# Fascia_physioBoardV0.net
KiCad netlist of a schematic drawn in EAGLE
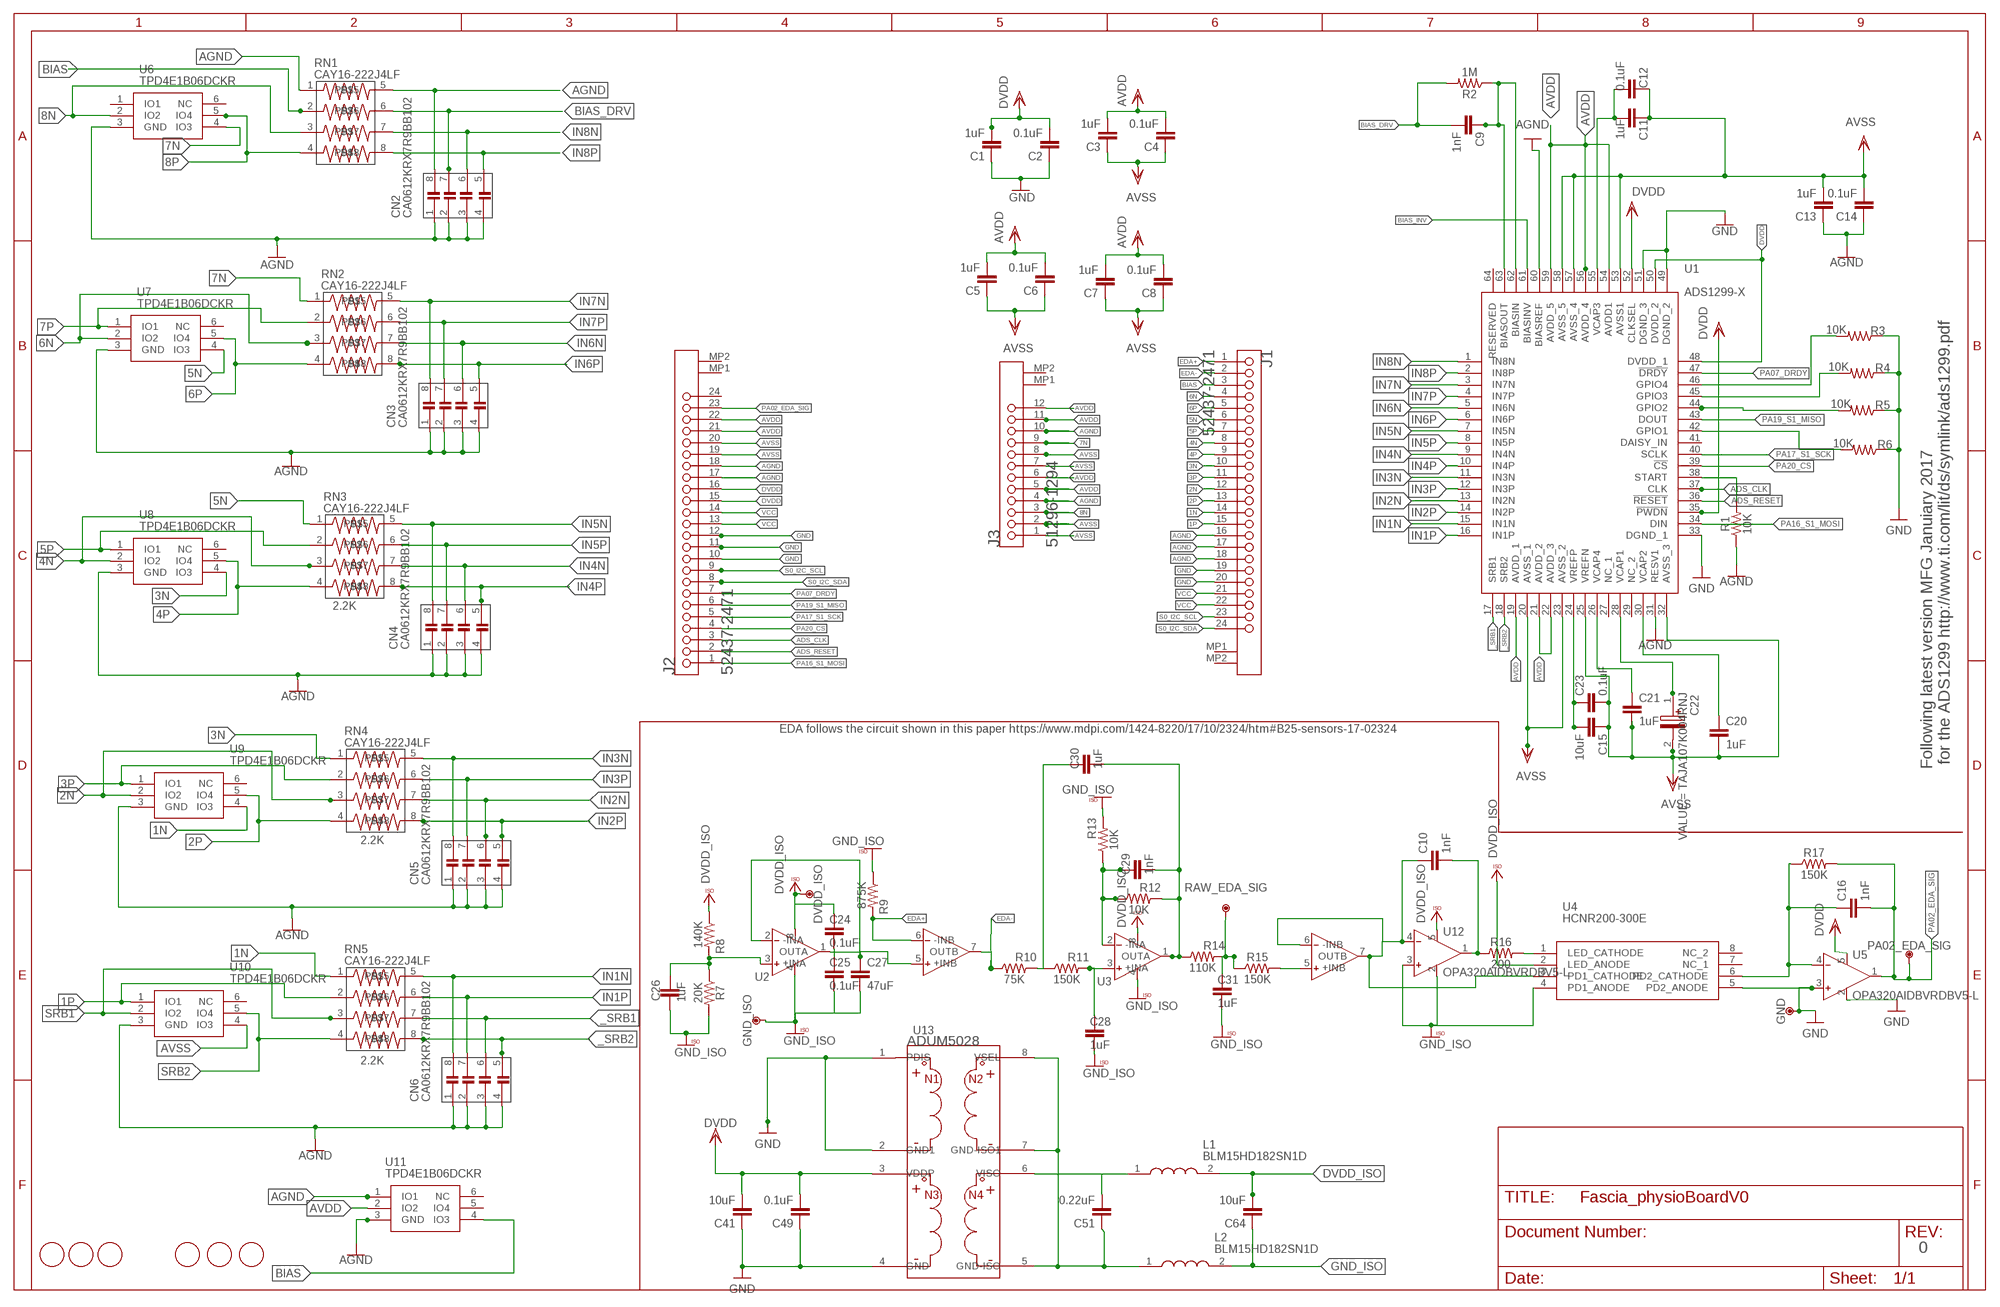
[diagram p0: schematic, sheet 1]

(export (version "E")
  (design (tool "Eeschema 10.0.6"))
  (components
    (comp (ref "C1")
      (value "1uF")
      (footprint "eagle-import:0402-TIGHT")
      (libsource (lib "eagle-import") (part "1UF-0402T-16V-10%"))
    )
    (comp (ref "C2")
      (value "0.1uF")
      (footprint "eagle-import:0402-TIGHT")
      (libsource (lib "eagle-import") (part "0.1UF-0402T-16V-10%"))
    )
    (comp (ref "C3")
      (value "1uF")
      (footprint "eagle-import:0402-TIGHT")
      (libsource (lib "eagle-import") (part "1UF-0402T-16V-10%"))
    )
    (comp (ref "C4")
      (value "0.1uF")
      (footprint "eagle-import:0402-TIGHT")
      (libsource (lib "eagle-import") (part "0.1UF-0402T-16V-10%"))
    )
    (comp (ref "C5")
      (value "1uF")
      (footprint "eagle-import:0402-TIGHT")
      (libsource (lib "eagle-import") (part "1UF-0402T-16V-10%"))
    )
    (comp (ref "C6")
      (value "0.1uF")
      (footprint "eagle-import:0402-TIGHT")
      (libsource (lib "eagle-import") (part "0.1UF-0402T-16V-10%"))
    )
    (comp (ref "C7")
      (value "1uF")
      (footprint "eagle-import:0402-TIGHT")
      (libsource (lib "eagle-import") (part "1UF-0402T-16V-10%"))
    )
    (comp (ref "C8")
      (value "0.1uF")
      (footprint "eagle-import:0402-TIGHT")
      (libsource (lib "eagle-import") (part "0.1UF-0402T-16V-10%"))
    )
    (comp (ref "C9")
      (value "1nF")
      (footprint "eagle-import:0402-TIGHT")
      (libsource (lib "eagle-import") (part "1NF-0402T-16V-10%"))
    )
    (comp (ref "C10")
      (value "1nF")
      (footprint "eagle-import:0402-TIGHT")
      (libsource (lib "eagle-import") (part "1NF-0402T-16V-10%"))
    )
    (comp (ref "C11")
      (value "1uF")
      (footprint "eagle-import:0402-TIGHT")
      (libsource (lib "eagle-import") (part "1UF-0402T-16V-10%"))
    )
    (comp (ref "C12")
      (value "0.1uF")
      (footprint "eagle-import:0402-TIGHT")
      (libsource (lib "eagle-import") (part "0.1UF-0402T-16V-10%"))
    )
    (comp (ref "C13")
      (value "1uF")
      (footprint "eagle-import:0402-TIGHT")
      (libsource (lib "eagle-import") (part "1UF-0402T-16V-10%"))
    )
    (comp (ref "C14")
      (value "0.1uF")
      (footprint "eagle-import:0402-TIGHT")
      (libsource (lib "eagle-import") (part "0.1UF-0402T-16V-10%"))
    )
    (comp (ref "C15")
      (value "10uF")
      (footprint "eagle-import:0402")
      (libsource (lib "eagle-import") (part "0.1UF-0402-16V-10%"))
    )
    (comp (ref "C16")
      (value "1nF")
      (footprint "eagle-import:0402-TIGHT")
      (libsource (lib "eagle-import") (part "1NF-0402T-16V-10%"))
    )
    (comp (ref "C20")
      (value "1uF")
      (footprint "eagle-import:0402-TIGHT")
      (libsource (lib "eagle-import") (part "1UF-0402T-16V-10%"))
    )
    (comp (ref "C21")
      (value "1uF")
      (footprint "eagle-import:0402-TIGHT")
      (libsource (lib "eagle-import") (part "1UF-0402T-16V-10%"))
    )
    (comp (ref "C22")
      (value "TAJA107K004RNJ")
      (footprint "eagle-import:CAPPM3216X180N")
      (fields
        (field (name "MOUSER_PART_NUMBER") "581-TAJA107K004RNJ")
        (field (name "RS_PART_NUMBER") "1360130")
      )
      (libsource (lib "eagle-import") (part "TAJA107K004RNJ"))
    )
    (comp (ref "C23")
      (value "0.1uF")
      (footprint "eagle-import:0402-TIGHT")
      (libsource (lib "eagle-import") (part "0.1UF-0402T-16V-10%"))
    )
    (comp (ref "C24")
      (value "0.1uF")
      (footprint "eagle-import:0402-TIGHT")
      (libsource (lib "eagle-import") (part "0.1UF-0402T-16V-10%"))
    )
    (comp (ref "C25")
      (value "0.1uF")
      (footprint "eagle-import:0402-TIGHT")
      (libsource (lib "eagle-import") (part "0.1UF-0402T-16V-10%"))
    )
    (comp (ref "C26")
      (value "1uF")
      (footprint "eagle-import:0402-TIGHT")
      (libsource (lib "eagle-import") (part "1UF-0402T-16V-10%"))
    )
    (comp (ref "C27")
      (value "47uF")
      (footprint "eagle-import:0603")
      (libsource (lib "eagle-import") (part "47UF-0603-25V-5%"))
    )
    (comp (ref "C28")
      (value "1uF")
      (footprint "eagle-import:0402-TIGHT")
      (libsource (lib "eagle-import") (part "1UF-0402T-16V-10%"))
    )
    (comp (ref "C29")
      (value "1nF")
      (footprint "eagle-import:0402-TIGHT")
      (libsource (lib "eagle-import") (part "1NF-0402T-16V-10%"))
    )
    (comp (ref "C30")
      (value "1uF")
      (footprint "eagle-import:0402-TIGHT")
      (libsource (lib "eagle-import") (part "1UF-0402T-16V-10%"))
    )
    (comp (ref "C31")
      (value "1uF")
      (footprint "eagle-import:0402-TIGHT")
      (libsource (lib "eagle-import") (part "1UF-0402T-16V-10%"))
    )
    (comp (ref "C41")
      (value "10uF")
      (footprint "eagle-import:0603")
      (libsource (lib "eagle-import") (part "10UF-0603-6.3V-20%"))
    )
    (comp (ref "C49")
      (value "0.1uF")
      (footprint "eagle-import:0402-TIGHT")
      (libsource (lib "eagle-import") (part "0.1UF-0402T-16V-10%"))
    )
    (comp (ref "C51")
      (value "0.22uF")
      (footprint "eagle-import:0402-TIGHT")
      (libsource (lib "eagle-import") (part "0.22UF-0402T-16V-10%"))
    )
    (comp (ref "C64")
      (value "10uF")
      (footprint "eagle-import:0603")
      (libsource (lib "eagle-import") (part "10UF-0603-6.3V-20%"))
    )
    (comp (ref "CN2")
      (value "CA0612KRX7R9BB102")
      (footprint "eagle-import:CA0612KRX7R9BB102")
      (fields
        (field (name "MOUSER_PART_NUMBER") "603-CA612KRX7R9BB102")
        (field (name "RS_PART_NUMBER") "6169789")
      )
      (libsource (lib "eagle-import") (part "CA0612KRX7R9BB102"))
    )
    (comp (ref "CN3")
      (value "CA0612KRX7R9BB102")
      (footprint "eagle-import:CA0612KRX7R9BB102")
      (fields
        (field (name "MOUSER_PART_NUMBER") "603-CA612KRX7R9BB102")
        (field (name "RS_PART_NUMBER") "6169789")
      )
      (libsource (lib "eagle-import") (part "CA0612KRX7R9BB102"))
    )
    (comp (ref "CN4")
      (value "CA0612KRX7R9BB102")
      (footprint "eagle-import:CA0612KRX7R9BB102")
      (fields
        (field (name "MOUSER_PART_NUMBER") "603-CA612KRX7R9BB102")
        (field (name "RS_PART_NUMBER") "6169789")
      )
      (libsource (lib "eagle-import") (part "CA0612KRX7R9BB102"))
    )
    (comp (ref "CN5")
      (value "CA0612KRX7R9BB102")
      (footprint "eagle-import:CA0612KRX7R9BB102")
      (fields
        (field (name "MOUSER_PART_NUMBER") "603-CA612KRX7R9BB102")
        (field (name "RS_PART_NUMBER") "6169789")
      )
      (libsource (lib "eagle-import") (part "CA0612KRX7R9BB102"))
    )
    (comp (ref "CN6")
      (value "CA0612KRX7R9BB102")
      (footprint "eagle-import:CA0612KRX7R9BB102")
      (fields
        (field (name "MOUSER_PART_NUMBER") "603-CA612KRX7R9BB102")
        (field (name "RS_PART_NUMBER") "6169789")
      )
      (libsource (lib "eagle-import") (part "CA0612KRX7R9BB102"))
    )
    (comp (ref "DVDD_ISO")
      (value "DNP")
      (footprint "eagle-import:TP-0.8MM")
      (libsource (lib "eagle-import") (part "TPTP-0.8MM"))
    )
    (comp (ref "FD1")
      (value "DNP")
      (footprint "eagle-import:FD-1-1.5")
      (libsource (lib "eagle-import") (part "FIDUCIAL-1.5MM"))
    )
    (comp (ref "FD2")
      (value "DNP")
      (footprint "eagle-import:FD-1-1.5")
      (libsource (lib "eagle-import") (part "FIDUCIAL-1.5MM"))
    )
    (comp (ref "FD3")
      (value "DNP")
      (footprint "eagle-import:FD-1-1.5")
      (libsource (lib "eagle-import") (part "FIDUCIAL-1.5MM"))
    )
    (comp (ref "FD4")
      (value "DNP")
      (footprint "eagle-import:FD-1-1.5")
      (libsource (lib "eagle-import") (part "FIDUCIAL-1.5MM"))
    )
    (comp (ref "FD5")
      (value "DNP")
      (footprint "eagle-import:FD-1-1.5")
      (libsource (lib "eagle-import") (part "FIDUCIAL-1.5MM"))
    )
    (comp (ref "FD6")
      (value "DNP")
      (footprint "eagle-import:FD-1-1.5")
      (libsource (lib "eagle-import") (part "FIDUCIAL-1.5MM"))
    )
    (comp (ref "GND")
      (value "DNP")
      (footprint "eagle-import:TP-0.8MM")
      (libsource (lib "eagle-import") (part "TPTP-0.8MM"))
    )
    (comp (ref "GND_ISO")
      (value "DNP")
      (footprint "eagle-import:TP-0.8MM")
      (libsource (lib "eagle-import") (part "TPTP-0.8MM"))
    )
    (comp (ref "J1")
      (value "MOLEX_52437-2471MOLEX_52437-2471_0_0")
      (footprint "eagle-import:MOLEX_52437-2471_0")
      (fields (field (name "MF") "Molex") (field (name "MPN") "52437-2471"))
      (libsource (lib "eagle-import") (part "MOLEX_52437-2471MOLEX_52437-2471_0_0"))
    )
    (comp (ref "J2")
      (value "MOLEX_52437-2471MOLEX_52437-2471_0_0")
      (footprint "eagle-import:MOLEX_52437-2471_0")
      (fields (field (name "MF") "Molex") (field (name "MPN") "52437-2471"))
      (libsource (lib "eagle-import") (part "MOLEX_52437-2471MOLEX_52437-2471_0_0"))
    )
    (comp (ref "J3")
      (value "MOLEX_51296-1294MOLEX_51296-1294_0_0")
      (footprint "eagle-import:MOLEX_51296-1294_0")
      (fields (field (name "MF") "Molex") (field (name "MPN") "51296-1294"))
      (libsource (lib "eagle-import") (part "MOLEX_51296-1294MOLEX_51296-1294_0_0"))
    )
    (comp (ref "L1")
      (value "BLM15HD182SN1D")
      (footprint "eagle-import:INDC1005X55N")
      (fields
        (field (name "MOUSER_PART_NUMBER") "81-BLM15HD182SN1D")
        (field (name "RS_PART_NUMBER") "7926224P")
      )
      (libsource (lib "eagle-import") (part "BLM15HD182SN1D"))
    )
    (comp (ref "L2")
      (value "BLM15HD182SN1D")
      (footprint "eagle-import:INDC1005X55N")
      (fields
        (field (name "MOUSER_PART_NUMBER") "81-BLM15HD182SN1D")
        (field (name "RS_PART_NUMBER") "7926224P")
      )
      (libsource (lib "eagle-import") (part "BLM15HD182SN1D"))
    )
    (comp (ref "PA02_EDA_SIG")
      (value "DNP")
      (footprint "eagle-import:TP-0.8MM")
      (libsource (lib "eagle-import") (part "TPTP-0.8MM"))
    )
    (comp (ref "R1")
      (value "10K")
      (footprint "eagle-import:0402-TIGHT")
      (libsource (lib "eagle-import") (part "10K"))
    )
    (comp (ref "R2")
      (value "1M")
      (footprint "eagle-import:0402-TIGHT")
      (libsource (lib "eagle-import") (part "1M"))
    )
    (comp (ref "R3")
      (value "10K")
      (footprint "eagle-import:0402-TIGHT")
      (libsource (lib "eagle-import") (part "10K"))
    )
    (comp (ref "R4")
      (value "10K")
      (footprint "eagle-import:0402-TIGHT")
      (libsource (lib "eagle-import") (part "10K"))
    )
    (comp (ref "R5")
      (value "10K")
      (footprint "eagle-import:0402-TIGHT")
      (libsource (lib "eagle-import") (part "10K"))
    )
    (comp (ref "R6")
      (value "10K")
      (footprint "eagle-import:0402-TIGHT")
      (libsource (lib "eagle-import") (part "10K"))
    )
    (comp (ref "R7")
      (value "20K")
      (footprint "eagle-import:0402-TIGHT")
      (libsource (lib "eagle-import") (part "20K"))
    )
    (comp (ref "R8")
      (value "140K")
      (footprint "eagle-import:0402-TIGHT")
      (libsource (lib "eagle-import") (part "140K"))
    )
    (comp (ref "R9")
      (value "875K")
      (footprint "eagle-import:0402-TIGHT")
      (libsource (lib "eagle-import") (part "875K"))
    )
    (comp (ref "R10")
      (value "75K")
      (footprint "eagle-import:0402-TIGHT")
      (libsource (lib "eagle-import") (part "75K"))
    )
    (comp (ref "R11")
      (value "150K")
      (footprint "eagle-import:0402-TIGHT")
      (libsource (lib "eagle-import") (part "150K"))
    )
    (comp (ref "R12")
      (value "10K")
      (footprint "eagle-import:0402-TIGHT")
      (libsource (lib "eagle-import") (part "10K"))
    )
    (comp (ref "R13")
      (value "10K")
      (footprint "eagle-import:0402-TIGHT")
      (libsource (lib "eagle-import") (part "10K"))
    )
    (comp (ref "R14")
      (value "110K")
      (footprint "eagle-import:0402-TIGHT")
      (libsource (lib "eagle-import") (part "110K"))
    )
    (comp (ref "R15")
      (value "150K")
      (footprint "eagle-import:0402-TIGHT")
      (libsource (lib "eagle-import") (part "150K"))
    )
    (comp (ref "R16")
      (value "200")
      (footprint "eagle-import:0402-TIGHT")
      (libsource (lib "eagle-import") (part "200"))
    )
    (comp (ref "R17")
      (value "150K")
      (footprint "eagle-import:0402-TIGHT")
      (libsource (lib "eagle-import") (part "150K"))
    )
    (comp (ref "RAW_EDA_SIG")
      (value "DNP")
      (footprint "eagle-import:TP-0.8MM")
      (libsource (lib "eagle-import") (part "TPTP-0.8MM"))
    )
    (comp (ref "RN1")
      (value "CAY16-222J4LF")
      (footprint "eagle-import:CAY16-222J4LF")
      (fields (field (name "MANUFACTURER_PART_NUMBER") "CAY16-222J4LF  "))
      (libsource (lib "eagle-import") (part "CAY16-222J4LF"))
    )
    (comp (ref "RN2")
      (value "CAY16-222J4LF")
      (footprint "eagle-import:CAY16-222J4LF")
      (fields (field (name "MANUFACTURER_PART_NUMBER") "CAY16-222J4LF  "))
      (libsource (lib "eagle-import") (part "CAY16-222J4LF"))
    )
    (comp (ref "RN3")
      (value "CAY16-222J4LF")
      (footprint "eagle-import:CAY16-222J4LF")
      (fields (field (name "MANUFACTURER_PART_NUMBER") "CAY16-222J4LF  "))
      (libsource (lib "eagle-import") (part "CAY16-222J4LF"))
    )
    (comp (ref "RN4")
      (value "CAY16-222J4LF")
      (footprint "eagle-import:CAY16-222J4LF")
      (fields (field (name "MANUFACTURER_PART_NUMBER") "CAY16-222J4LF  "))
      (libsource (lib "eagle-import") (part "CAY16-222J4LF"))
    )
    (comp (ref "RN5")
      (value "CAY16-222J4LF")
      (footprint "eagle-import:CAY16-222J4LF")
      (fields (field (name "MANUFACTURER_PART_NUMBER") "CAY16-222J4LF  "))
      (libsource (lib "eagle-import") (part "CAY16-222J4LF"))
    )
    (comp (ref "U1")
      (value "ADS1299-X")
      (footprint "eagle-import:QFP50P1200X1200X120-64N")
      (libsource (lib "eagle-import") (part "ADS1299-X"))
    )
    (comp (ref "U2")
      (value "OPA2320AIDGKT_NOVA8-SOIC-L")
      (footprint "eagle-import:D8-L")
      (libsource (lib "eagle-import") (part "OPA2320AIDGKT_NOVA8-SOIC-L"))
    )
    (comp (ref "U3")
      (value "OPA2320AIDGKT_NOVAL8-SOIC-L")
      (footprint "eagle-import:D8-L")
      (libsource (lib "eagle-import") (part "OPA2320AIDGKT_NOVAL8-SOIC-L"))
    )
    (comp (ref "U4")
      (value "HCNR200-300E")
      (footprint "eagle-import:SOP254P1230X400-8N")
      (fields
        (field (name "MOUSER_PART_NUMBER") "630-HCNR200-300E")
        (field (name "RS_PART_NUMBER") "6935264P")
      )
      (libsource (lib "eagle-import") (part "HCNR200-300E"))
    )
    (comp (ref "U5")
      (value "OPA320AIDBVRDBV5-L")
      (footprint "eagle-import:DBV5-L")
      (fields (field (name "MANUFACTURER_PART_NUMBER") "OPA320AIDBVR"))
      (libsource (lib "eagle-import") (part "OPA320AIDBVRDBV5-L"))
    )
    (comp (ref "U6")
      (value "TPD4E1B06DCKR")
      (footprint "eagle-import:SOT65P210X110-6N")
      (fields
        (field (name "MOUSER_PART_NUMBER") "595-TPD4E1B06DCKR")
        (field (name "RS_PART_NUMBER") "8255330P")
      )
      (libsource (lib "eagle-import") (part "TPD4E1B06DCKR"))
    )
    (comp (ref "U7")
      (value "TPD4E1B06DCKR")
      (footprint "eagle-import:SOT65P210X110-6N")
      (fields
        (field (name "MOUSER_PART_NUMBER") "595-TPD4E1B06DCKR")
        (field (name "RS_PART_NUMBER") "8255330P")
      )
      (libsource (lib "eagle-import") (part "TPD4E1B06DCKR"))
    )
    (comp (ref "U8")
      (value "TPD4E1B06DCKR")
      (footprint "eagle-import:SOT65P210X110-6N")
      (fields
        (field (name "MOUSER_PART_NUMBER") "595-TPD4E1B06DCKR")
        (field (name "RS_PART_NUMBER") "8255330P")
      )
      (libsource (lib "eagle-import") (part "TPD4E1B06DCKR"))
    )
    (comp (ref "U9")
      (value "TPD4E1B06DCKR")
      (footprint "eagle-import:SOT65P210X110-6N")
      (fields
        (field (name "MOUSER_PART_NUMBER") "595-TPD4E1B06DCKR")
        (field (name "RS_PART_NUMBER") "8255330P")
      )
      (libsource (lib "eagle-import") (part "TPD4E1B06DCKR"))
    )
    (comp (ref "U10")
      (value "TPD4E1B06DCKR")
      (footprint "eagle-import:SOT65P210X110-6N")
      (fields
        (field (name "MOUSER_PART_NUMBER") "595-TPD4E1B06DCKR")
        (field (name "RS_PART_NUMBER") "8255330P")
      )
      (libsource (lib "eagle-import") (part "TPD4E1B06DCKR"))
    )
    (comp (ref "U11")
      (value "TPD4E1B06DCKR")
      (footprint "eagle-import:SOT65P210X110-6N")
      (fields
        (field (name "MOUSER_PART_NUMBER") "595-TPD4E1B06DCKR")
        (field (name "RS_PART_NUMBER") "8255330P")
      )
      (libsource (lib "eagle-import") (part "TPD4E1B06DCKR"))
    )
    (comp (ref "U12")
      (value "OPA320AIDBVRDBV5-L")
      (footprint "eagle-import:DBV5-L")
      (fields (field (name "MANUFACTURER_PART_NUMBER") "OPA320AIDBVR"))
      (libsource (lib "eagle-import") (part "OPA320AIDBVRDBV5-L"))
    )
    (comp (ref "U13")
      (value "ADUM5028")
      (footprint "eagle-import:SOIC_IC")
      (libsource (lib "eagle-import") (part "ADUM5028"))
    )
  )
  (nets
    (net (code "1") (name "1N") (class "Default")
      (node (ref "J1") (pin "14") (pinfunction "14_14") (pintype "passive"))
      (node (ref "RN5") (pin "1") (pinfunction "P$1_1") (pintype "bidirectional"))
      (node (ref "U9") (pin "4") (pinfunction "IO3_4") (pintype "bidirectional"))
    )
    (net (code "2") (name "1P") (class "Default")
      (node (ref "J1") (pin "15") (pinfunction "15_15") (pintype "passive"))
      (node (ref "RN5") (pin "2") (pinfunction "P$2_2") (pintype "bidirectional"))
      (node (ref "U10") (pin "1") (pinfunction "IO1_1") (pintype "bidirectional"))
    )
    (net (code "3") (name "2N") (class "Default")
      (node (ref "J1") (pin "12") (pinfunction "12_12") (pintype "passive"))
      (node (ref "RN4") (pin "3") (pinfunction "P$3_3") (pintype "bidirectional"))
      (node (ref "U9") (pin "2") (pinfunction "IO2_2") (pintype "bidirectional"))
    )
    (net (code "4") (name "2P") (class "Default")
      (node (ref "J1") (pin "13") (pinfunction "13_13") (pintype "passive"))
      (node (ref "RN4") (pin "4") (pinfunction "P$4_4") (pintype "bidirectional"))
      (node (ref "U9") (pin "5") (pinfunction "IO4_5") (pintype "bidirectional"))
    )
    (net (code "5") (name "3N") (class "Default")
      (node (ref "J1") (pin "10") (pinfunction "10_10") (pintype "passive"))
      (node (ref "RN4") (pin "1") (pinfunction "P$1_1") (pintype "bidirectional"))
      (node (ref "U8") (pin "4") (pinfunction "IO3_4") (pintype "bidirectional"))
    )
    (net (code "6") (name "3P") (class "Default")
      (node (ref "J1") (pin "11") (pinfunction "11_11") (pintype "passive"))
      (node (ref "RN4") (pin "2") (pinfunction "P$2_2") (pintype "bidirectional"))
      (node (ref "U9") (pin "1") (pinfunction "IO1_1") (pintype "bidirectional"))
    )
    (net (code "7") (name "4N") (class "Default")
      (node (ref "J1") (pin "8") (pinfunction "8_8") (pintype "passive"))
      (node (ref "RN3") (pin "3") (pinfunction "P$3_3") (pintype "bidirectional"))
      (node (ref "U8") (pin "2") (pinfunction "IO2_2") (pintype "bidirectional"))
    )
    (net (code "8") (name "4P") (class "Default")
      (node (ref "J1") (pin "9") (pinfunction "9_9") (pintype "passive"))
      (node (ref "RN3") (pin "4") (pinfunction "P$4_4") (pintype "bidirectional"))
      (node (ref "U8") (pin "5") (pinfunction "IO4_5") (pintype "bidirectional"))
    )
    (net (code "9") (name "5N") (class "Default")
      (node (ref "J1") (pin "6") (pinfunction "6_6") (pintype "passive"))
      (node (ref "RN3") (pin "1") (pinfunction "P$1_1") (pintype "bidirectional"))
      (node (ref "U7") (pin "4") (pinfunction "IO3_4") (pintype "bidirectional"))
    )
    (net (code "10") (name "5P") (class "Default")
      (node (ref "J1") (pin "7") (pinfunction "7_7") (pintype "passive"))
      (node (ref "RN3") (pin "2") (pinfunction "P$2_2") (pintype "bidirectional"))
      (node (ref "U8") (pin "1") (pinfunction "IO1_1") (pintype "bidirectional"))
    )
    (net (code "11") (name "6N") (class "Default")
      (node (ref "J1") (pin "4") (pinfunction "4_4") (pintype "passive"))
      (node (ref "RN2") (pin "3") (pinfunction "P$3_3") (pintype "bidirectional"))
      (node (ref "U7") (pin "2") (pinfunction "IO2_2") (pintype "bidirectional"))
    )
    (net (code "12") (name "6P") (class "Default")
      (node (ref "J1") (pin "5") (pinfunction "5_5") (pintype "passive"))
      (node (ref "RN2") (pin "4") (pinfunction "P$4_4") (pintype "bidirectional"))
      (node (ref "U7") (pin "5") (pinfunction "IO4_5") (pintype "bidirectional"))
    )
    (net (code "13") (name "7N") (class "Default")
      (node (ref "J3") (pin "9") (pinfunction "9_9") (pintype "passive"))
      (node (ref "RN2") (pin "1") (pinfunction "P$1_1") (pintype "bidirectional"))
      (node (ref "U6") (pin "4") (pinfunction "IO3_4") (pintype "bidirectional"))
    )
    (net (code "14") (name "7P") (class "Default")
      (node (ref "RN2") (pin "2") (pinfunction "P$2_2") (pintype "bidirectional"))
      (node (ref "U7") (pin "1") (pinfunction "IO1_1") (pintype "bidirectional"))
    )
    (net (code "15") (name "8N") (class "Default")
      (node (ref "J3") (pin "3") (pinfunction "3_3") (pintype "passive"))
      (node (ref "RN1") (pin "3") (pinfunction "P$3_3") (pintype "bidirectional"))
      (node (ref "U6") (pin "2") (pinfunction "IO2_2") (pintype "bidirectional"))
    )
    (net (code "16") (name "8P") (class "Default")
      (node (ref "RN1") (pin "4") (pinfunction "P$4_4") (pintype "bidirectional"))
      (node (ref "U6") (pin "5") (pinfunction "IO4_5") (pintype "bidirectional"))
    )
    (net (code "17") (name "ADS_CLK") (class "Default")
      (node (ref "J2") (pin "3") (pinfunction "3_3") (pintype "passive"))
      (node (ref "U1") (pin "37") (pinfunction "CLK_37") (pintype "bidirectional"))
    )
    (net (code "18") (name "ADS_RESET") (class "Default")
      (node (ref "J2") (pin "2") (pinfunction "2_2") (pintype "passive"))
      (node (ref "U1") (pin "36") (pinfunction "~{RESET}_36") (pintype "bidirectional"))
    )
    (net (code "19") (name "AGND") (class "Default")
      (node (ref "C13") (pin "1") (pinfunction "1_1") (pintype "passive"))
      (node (ref "C14") (pin "1") (pinfunction "1_1") (pintype "passive"))
      (node (ref "CN2") (pin "1") (pinfunction "C10_1") (pintype "bidirectional"))
      (node (ref "CN2") (pin "2") (pinfunction "C11_2") (pintype "bidirectional"))
      (node (ref "CN2") (pin "3") (pinfunction "C12_3") (pintype "bidirectional"))
      (node (ref "CN2") (pin "4") (pinfunction "C13_4") (pintype "bidirectional"))
      (node (ref "CN2") (pin "8") (pinfunction "C17_8") (pintype "bidirectional"))
      (node (ref "CN3") (pin "1") (pinfunction "C10_1") (pintype "bidirectional"))
      (node (ref "CN3") (pin "2") (pinfunction "C11_2") (pintype "bidirectional"))
      (node (ref "CN3") (pin "3") (pinfunction "C12_3") (pintype "bidirectional"))
      (node (ref "CN3") (pin "4") (pinfunction "C13_4") (pintype "bidirectional"))
      (node (ref "CN4") (pin "1") (pinfunction "C10_1") (pintype "bidirectional"))
      (node (ref "CN4") (pin "2") (pinfunction "C11_2") (pintype "bidirectional"))
      (node (ref "CN4") (pin "3") (pinfunction "C12_3") (pintype "bidirectional"))
      (node (ref "CN4") (pin "4") (pinfunction "C13_4") (pintype "bidirectional"))
      (node (ref "CN5") (pin "1") (pinfunction "C10_1") (pintype "bidirectional"))
      (node (ref "CN5") (pin "2") (pinfunction "C11_2") (pintype "bidirectional"))
      (node (ref "CN5") (pin "3") (pinfunction "C12_3") (pintype "bidirectional"))
      (node (ref "CN5") (pin "4") (pinfunction "C13_4") (pintype "bidirectional"))
      (node (ref "CN6") (pin "1") (pinfunction "C10_1") (pintype "bidirectional"))
      (node (ref "CN6") (pin "2") (pinfunction "C11_2") (pintype "bidirectional"))
      (node (ref "CN6") (pin "3") (pinfunction "C12_3") (pintype "bidirectional"))
      (node (ref "CN6") (pin "4") (pinfunction "C13_4") (pintype "bidirectional"))
      (node (ref "J1") (pin "16") (pinfunction "16_16") (pintype "passive"))
      (node (ref "J1") (pin "17") (pinfunction "17_17") (pintype "passive"))
      (node (ref "J1") (pin "18") (pinfunction "18_18") (pintype "passive"))
      (node (ref "J2") (pin "17") (pinfunction "17_17") (pintype "passive"))
      (node (ref "J2") (pin "18") (pinfunction "18_18") (pintype "passive"))
      (node (ref "J3") (pin "10") (pinfunction "10_10") (pintype "passive"))
      (node (ref "J3") (pin "4") (pinfunction "4_4") (pintype "passive"))
      (node (ref "R1") (pin "1") (pinfunction "1_1") (pintype "passive"))
      (node (ref "RN1") (pin "1") (pinfunction "P$1_1") (pintype "bidirectional"))
      (node (ref "RN1") (pin "5") (pinfunction "P$5_5") (pintype "bidirectional"))
      (node (ref "U1") (pin "31") (pinfunction "RESV1_31") (pintype "bidirectional"))
      (node (ref "U1") (pin "60") (pinfunction "BIASREF_60") (pintype "bidirectional"))
      (node (ref "U10") (pin "3") (pinfunction "GND_3") (pintype "power_in"))
      (node (ref "U11") (pin "1") (pinfunction "IO1_1") (pintype "bidirectional"))
      (node (ref "U11") (pin "3") (pinfunction "GND_3") (pintype "power_in"))
      (node (ref "U6") (pin "3") (pinfunction "GND_3") (pintype "power_in"))
      (node (ref "U7") (pin "3") (pinfunction "GND_3") (pintype "power_in"))
      (node (ref "U8") (pin "3") (pinfunction "GND_3") (pintype "power_in"))
      (node (ref "U9") (pin "3") (pinfunction "GND_3") (pintype "power_in"))
    )
    (net (code "20") (name "AVDD") (class "Default")
      (node (ref "C3") (pin "2") (pinfunction "2_2") (pintype "passive"))
      (node (ref "C4") (pin "2") (pinfunction "2_2") (pintype "passive"))
      (node (ref "C5") (pin "2") (pinfunction "2_2") (pintype "passive"))
      (node (ref "C6") (pin "2") (pinfunction "2_2") (pintype "passive"))
      (node (ref "C7") (pin "2") (pinfunction "2_2") (pintype "passive"))
      (node (ref "C8") (pin "2") (pinfunction "2_2") (pintype "passive"))
      (node (ref "J2") (pin "21") (pinfunction "21_21") (pintype "passive"))
      (node (ref "J2") (pin "22") (pinfunction "22_22") (pintype "passive"))
      (node (ref "J3") (pin "11") (pinfunction "11_11") (pintype "passive"))
      (node (ref "J3") (pin "12") (pinfunction "12_12") (pintype "passive"))
      (node (ref "J3") (pin "5") (pinfunction "5_5") (pintype "passive"))
      (node (ref "J3") (pin "6") (pinfunction "6_6") (pintype "passive"))
      (node (ref "U1") (pin "19") (pinfunction "AVDD_1_19") (pintype "bidirectional"))
      (node (ref "U1") (pin "21") (pinfunction "AVDD_2_21") (pintype "bidirectional"))
      (node (ref "U1") (pin "22") (pinfunction "AVDD_3_22") (pintype "bidirectional"))
      (node (ref "U1") (pin "54") (pinfunction "AVDD1_54") (pintype "bidirectional"))
      (node (ref "U1") (pin "56") (pinfunction "AVDD_4_56") (pintype "bidirectional"))
      (node (ref "U1") (pin "59") (pinfunction "AVDD_5_59") (pintype "bidirectional"))
      (node (ref "U11") (pin "2") (pinfunction "IO2_2") (pintype "bidirectional"))
    )
    (net (code "21") (name "AVSS") (class "Default")
      (node (ref "C11") (pin "1") (pinfunction "1_1") (pintype "passive"))
      (node (ref "C12") (pin "1") (pinfunction "1_1") (pintype "passive"))
      (node (ref "C13") (pin "2") (pinfunction "2_2") (pintype "passive"))
      (node (ref "C14") (pin "2") (pinfunction "2_2") (pintype "passive"))
      (node (ref "C15") (pin "1") (pinfunction "1_1") (pintype "passive"))
      (node (ref "C20") (pin "2") (pinfunction "2_2") (pintype "passive"))
      (node (ref "C21") (pin "2") (pinfunction "2_2") (pintype "passive"))
      (node (ref "C22") (pin "2") (pinfunction "-_2") (pintype "bidirectional"))
      (node (ref "C23") (pin "2") (pinfunction "2_2") (pintype "passive"))
      (node (ref "C3") (pin "1") (pinfunction "1_1") (pintype "passive"))
      (node (ref "C4") (pin "1") (pinfunction "1_1") (pintype "passive"))
      (node (ref "C5") (pin "1") (pinfunction "1_1") (pintype "passive"))
      (node (ref "C6") (pin "1") (pinfunction "1_1") (pintype "passive"))
      (node (ref "C7") (pin "1") (pinfunction "1_1") (pintype "passive"))
      (node (ref "C8") (pin "1") (pinfunction "1_1") (pintype "passive"))
      (node (ref "J2") (pin "19") (pinfunction "19_19") (pintype "passive"))
      (node (ref "J2") (pin "20") (pinfunction "20_20") (pintype "passive"))
      (node (ref "J3") (pin "1") (pinfunction "1_1") (pintype "passive"))
      (node (ref "J3") (pin "2") (pinfunction "2_2") (pintype "passive"))
      (node (ref "J3") (pin "7") (pinfunction "7_7") (pintype "passive"))
      (node (ref "J3") (pin "8") (pinfunction "8_8") (pintype "passive"))
      (node (ref "U1") (pin "20") (pinfunction "AVSS_1_20") (pintype "bidirectional"))
      (node (ref "U1") (pin "23") (pinfunction "AVSS_2_23") (pintype "bidirectional"))
      (node (ref "U1") (pin "25") (pinfunction "VREFN_25") (pintype "bidirectional"))
      (node (ref "U1") (pin "32") (pinfunction "AVSS_3_32") (pintype "bidirectional"))
      (node (ref "U1") (pin "53") (pinfunction "AVSS1_53") (pintype "bidirectional"))
      (node (ref "U1") (pin "57") (pinfunction "AVSS_4_57") (pintype "bidirectional"))
      (node (ref "U1") (pin "58") (pinfunction "AVSS_5_58") (pintype "bidirectional"))
      (node (ref "U10") (pin "4") (pinfunction "IO3_4") (pintype "bidirectional"))
    )
    (net (code "22") (name "BIAS") (class "Default")
      (node (ref "J1") (pin "3") (pinfunction "3_3") (pintype "passive"))
      (node (ref "RN1") (pin "2") (pinfunction "P$2_2") (pintype "bidirectional"))
      (node (ref "U11") (pin "4") (pinfunction "IO3_4") (pintype "bidirectional"))
    )
    (net (code "23") (name "BIAS_DRV") (class "Default")
      (node (ref "C9") (pin "2") (pinfunction "2_2") (pintype "passive"))
      (node (ref "CN2") (pin "7") (pinfunction "C16_7") (pintype "bidirectional"))
      (node (ref "R2") (pin "2") (pinfunction "2_2") (pintype "passive"))
      (node (ref "RN1") (pin "6") (pinfunction "P$6_6") (pintype "bidirectional"))
    )
    (net (code "24") (name "BIAS_INV") (class "Default")
      (node (ref "U1") (pin "61") (pinfunction "BIASINV_61") (pintype "bidirectional"))
    )
    (net (code "25") (name "DVDD") (class "Default")
      (node (ref "C1") (pin "2") (pinfunction "2_2") (pintype "passive"))
      (node (ref "C2") (pin "2") (pinfunction "2_2") (pintype "passive"))
      (node (ref "C41") (pin "2") (pinfunction "2_2") (pintype "passive"))
      (node (ref "C49") (pin "2") (pinfunction "2_2") (pintype "passive"))
      (node (ref "J2") (pin "15") (pinfunction "15_15") (pintype "passive"))
      (node (ref "J2") (pin "16") (pinfunction "16_16") (pintype "passive"))
      (node (ref "U1") (pin "35") (pinfunction "~{PWDN}_35") (pintype "bidirectional"))
      (node (ref "U1") (pin "48") (pinfunction "DVDD_1_48") (pintype "bidirectional"))
      (node (ref "U1") (pin "50") (pinfunction "DVDD_2_50") (pintype "bidirectional"))
      (node (ref "U1") (pin "52") (pinfunction "CLKSEL_52") (pintype "bidirectional"))
      (node (ref "U13") (pin "3") (pinfunction "VDDP_3") (pintype "bidirectional"))
      (node (ref "U5") (pin "5") (pinfunction "V+_5") (pintype "bidirectional"))
    )
    (net (code "26") (name "DVDD_ISO") (class "Default")
      (node (ref "C24") (pin "1") (pinfunction "1_1") (pintype "passive"))
      (node (ref "C64") (pin "2") (pinfunction "2_2") (pintype "passive"))
      (node (ref "DVDD_ISO") (pin "X") (pinfunction "P$1_X") (pintype "passive"))
      (node (ref "L1") (pin "2") (pinfunction "2_2") (pintype "bidirectional"))
      (node (ref "R8") (pin "1") (pinfunction "1_1") (pintype "passive"))
      (node (ref "U12") (pin "5") (pinfunction "V+_5") (pintype "bidirectional"))
      (node (ref "U2") (pin "8") (pinfunction "V+_8") (pintype "bidirectional"))
      (node (ref "U3") (pin "8") (pinfunction "V+_8") (pintype "bidirectional"))
      (node (ref "U4") (pin "2") (pinfunction "LED_ANODE_2") (pintype "bidirectional"))
    )
    (net (code "27") (name "EDA+") (class "Default")
      (node (ref "J1") (pin "1") (pinfunction "1_1") (pintype "passive"))
      (node (ref "R9") (pin "2") (pinfunction "2_2") (pintype "passive"))
      (node (ref "U2") (pin "6") (pinfunction "-INB_6") (pintype "input"))
    )
    (net (code "28") (name "EDA-") (class "Default")
      (node (ref "J1") (pin "2") (pinfunction "2_2") (pintype "passive"))
      (node (ref "R10") (pin "1") (pinfunction "1_1") (pintype "passive"))
      (node (ref "U2") (pin "7") (pinfunction "OUTB_7") (pintype "output"))
    )
    (net (code "29") (name "GND") (class "Default")
      (node (ref "C1") (pin "1") (pinfunction "1_1") (pintype "passive"))
      (node (ref "C2") (pin "1") (pinfunction "1_1") (pintype "passive"))
      (node (ref "C41") (pin "1") (pinfunction "1_1") (pintype "passive"))
      (node (ref "C49") (pin "1") (pinfunction "1_1") (pintype "passive"))
      (node (ref "GND") (pin "X") (pinfunction "P$1_X") (pintype "passive"))
      (node (ref "J1") (pin "19") (pinfunction "19_19") (pintype "passive"))
      (node (ref "J1") (pin "20") (pinfunction "20_20") (pintype "passive"))
      (node (ref "J2") (pin "10") (pinfunction "10_10") (pintype "passive"))
      (node (ref "J2") (pin "11") (pinfunction "11_11") (pintype "passive"))
      (node (ref "J2") (pin "12") (pinfunction "12_12") (pintype "passive"))
      (node (ref "R3") (pin "1") (pinfunction "1_1") (pintype "passive"))
      (node (ref "R4") (pin "1") (pinfunction "1_1") (pintype "passive"))
      (node (ref "R5") (pin "1") (pinfunction "1_1") (pintype "passive"))
      (node (ref "R6") (pin "1") (pinfunction "1_1") (pintype "passive"))
      (node (ref "U1") (pin "33") (pinfunction "DGND_1_33") (pintype "bidirectional"))
      (node (ref "U1") (pin "49") (pinfunction "DGND_2_49") (pintype "bidirectional"))
      (node (ref "U1") (pin "51") (pinfunction "DGND_3_51") (pintype "bidirectional"))
      (node (ref "U13") (pin "1") (pinfunction "PDIS_1") (pintype "bidirectional"))
      (node (ref "U13") (pin "2") (pinfunction "GND1_2") (pintype "bidirectional"))
      (node (ref "U13") (pin "4") (pinfunction "GND_4") (pintype "bidirectional"))
      (node (ref "U4") (pin "5") (pinfunction "PD2_ANODE_5") (pintype "bidirectional"))
      (node (ref "U5") (pin "2") (pinfunction "V-_2") (pintype "bidirectional"))
      (node (ref "U5") (pin "3") (pinfunction "IN+_3") (pintype "input"))
    )
    (net (code "30") (name "GND_ISO") (class "Default")
      (node (ref "C25") (pin "2") (pinfunction "2_2") (pintype "passive"))
      (node (ref "C26") (pin "2") (pinfunction "2_2") (pintype "passive"))
      (node (ref "C27") (pin "2") (pinfunction "2_2") (pintype "passive"))
      (node (ref "C28") (pin "2") (pinfunction "2_2") (pintype "passive"))
      (node (ref "C31") (pin "2") (pinfunction "2_2") (pintype "passive"))
      (node (ref "C51") (pin "1") (pinfunction "1_1") (pintype "passive"))
      (node (ref "C64") (pin "1") (pinfunction "1_1") (pintype "passive"))
      (node (ref "GND_ISO") (pin "X") (pinfunction "P$1_X") (pintype "passive"))
      (node (ref "L2") (pin "1") (pinfunction "1_1") (pintype "bidirectional"))
      (node (ref "L2") (pin "2") (pinfunction "2_2") (pintype "bidirectional"))
      (node (ref "R13") (pin "2") (pinfunction "2_2") (pintype "passive"))
      (node (ref "R7") (pin "2") (pinfunction "2_2") (pintype "passive"))
      (node (ref "R9") (pin "1") (pinfunction "1_1") (pintype "passive"))
      (node (ref "U12") (pin "2") (pinfunction "V-_2") (pintype "bidirectional"))
      (node (ref "U12") (pin "3") (pinfunction "IN+_3") (pintype "input"))
      (node (ref "U13") (pin "5") (pinfunction "GND-ISO_5") (pintype "bidirectional"))
      (node (ref "U13") (pin "7") (pinfunction "GND-ISO1_7") (pintype "bidirectional"))
      (node (ref "U13") (pin "8") (pinfunction "VSEL_8") (pintype "bidirectional"))
      (node (ref "U2") (pin "4") (pinfunction "V-_4") (pintype "bidirectional"))
      (node (ref "U3") (pin "4") (pinfunction "V-_4") (pintype "bidirectional"))
      (node (ref "U4") (pin "4") (pinfunction "PD1_ANODE_4") (pintype "bidirectional"))
    )
    (net (code "31") (name "IN1N") (class "Default")
      (node (ref "CN6") (pin "8") (pinfunction "C17_8") (pintype "bidirectional"))
      (node (ref "RN5") (pin "5") (pinfunction "P$5_5") (pintype "bidirectional"))
      (node (ref "U1") (pin "15") (pinfunction "IN1N_15") (pintype "bidirectional"))
    )
    (net (code "32") (name "IN1P") (class "Default")
      (node (ref "CN6") (pin "7") (pinfunction "C16_7") (pintype "bidirectional"))
      (node (ref "RN5") (pin "6") (pinfunction "P$6_6") (pintype "bidirectional"))
      (node (ref "U1") (pin "16") (pinfunction "IN1P_16") (pintype "bidirectional"))
    )
    (net (code "33") (name "IN2N") (class "Default")
      (node (ref "CN5") (pin "6") (pinfunction "C15_6") (pintype "bidirectional"))
      (node (ref "RN4") (pin "7") (pinfunction "P$7_7") (pintype "bidirectional"))
      (node (ref "U1") (pin "13") (pinfunction "IN2N_13") (pintype "bidirectional"))
    )
    (net (code "34") (name "IN2P") (class "Default")
      (node (ref "CN5") (pin "5") (pinfunction "C14_5") (pintype "bidirectional"))
      (node (ref "RN4") (pin "8") (pinfunction "P$8_8") (pintype "bidirectional"))
      (node (ref "U1") (pin "14") (pinfunction "IN2P_14") (pintype "bidirectional"))
    )
    (net (code "35") (name "IN3N") (class "Default")
      (node (ref "CN5") (pin "8") (pinfunction "C17_8") (pintype "bidirectional"))
      (node (ref "RN4") (pin "5") (pinfunction "P$5_5") (pintype "bidirectional"))
      (node (ref "U1") (pin "11") (pinfunction "IN3N_11") (pintype "bidirectional"))
    )
    (net (code "36") (name "IN3P") (class "Default")
      (node (ref "CN5") (pin "7") (pinfunction "C16_7") (pintype "bidirectional"))
      (node (ref "RN4") (pin "6") (pinfunction "P$6_6") (pintype "bidirectional"))
      (node (ref "U1") (pin "12") (pinfunction "IN3P_12") (pintype "bidirectional"))
    )
    (net (code "37") (name "IN4N") (class "Default")
      (node (ref "CN4") (pin "6") (pinfunction "C15_6") (pintype "bidirectional"))
      (node (ref "RN3") (pin "7") (pinfunction "P$7_7") (pintype "bidirectional"))
      (node (ref "U1") (pin "9") (pinfunction "IN4N_9") (pintype "bidirectional"))
    )
    (net (code "38") (name "IN4P") (class "Default")
      (node (ref "CN4") (pin "5") (pinfunction "C14_5") (pintype "bidirectional"))
      (node (ref "RN3") (pin "8") (pinfunction "P$8_8") (pintype "bidirectional"))
      (node (ref "U1") (pin "10") (pinfunction "IN4P_10") (pintype "bidirectional"))
    )
    (net (code "39") (name "IN5N") (class "Default")
      (node (ref "CN4") (pin "8") (pinfunction "C17_8") (pintype "bidirectional"))
      (node (ref "RN3") (pin "5") (pinfunction "P$5_5") (pintype "bidirectional"))
      (node (ref "U1") (pin "7") (pinfunction "IN5N_7") (pintype "bidirectional"))
    )
    (net (code "40") (name "IN5P") (class "Default")
      (node (ref "CN4") (pin "7") (pinfunction "C16_7") (pintype "bidirectional"))
      (node (ref "RN3") (pin "6") (pinfunction "P$6_6") (pintype "bidirectional"))
      (node (ref "U1") (pin "8") (pinfunction "IN5P_8") (pintype "bidirectional"))
    )
    (net (code "41") (name "IN6N") (class "Default")
      (node (ref "CN3") (pin "6") (pinfunction "C15_6") (pintype "bidirectional"))
      (node (ref "RN2") (pin "7") (pinfunction "P$7_7") (pintype "bidirectional"))
      (node (ref "U1") (pin "5") (pinfunction "IN6N_5") (pintype "bidirectional"))
    )
    (net (code "42") (name "IN6P") (class "Default")
      (node (ref "CN3") (pin "5") (pinfunction "C14_5") (pintype "bidirectional"))
      (node (ref "RN2") (pin "8") (pinfunction "P$8_8") (pintype "bidirectional"))
      (node (ref "U1") (pin "6") (pinfunction "IN6P_6") (pintype "bidirectional"))
    )
    (net (code "43") (name "IN7N") (class "Default")
      (node (ref "CN3") (pin "8") (pinfunction "C17_8") (pintype "bidirectional"))
      (node (ref "RN2") (pin "5") (pinfunction "P$5_5") (pintype "bidirectional"))
      (node (ref "U1") (pin "3") (pinfunction "IN7N_3") (pintype "bidirectional"))
    )
    (net (code "44") (name "IN7P") (class "Default")
      (node (ref "CN3") (pin "7") (pinfunction "C16_7") (pintype "bidirectional"))
      (node (ref "RN2") (pin "6") (pinfunction "P$6_6") (pintype "bidirectional"))
      (node (ref "U1") (pin "4") (pinfunction "IN7P_4") (pintype "bidirectional"))
    )
    (net (code "45") (name "IN8N") (class "Default")
      (node (ref "CN2") (pin "6") (pinfunction "C15_6") (pintype "bidirectional"))
      (node (ref "RN1") (pin "7") (pinfunction "P$7_7") (pintype "bidirectional"))
      (node (ref "U1") (pin "1") (pinfunction "IN8N_1") (pintype "bidirectional"))
    )
    (net (code "46") (name "IN8P") (class "Default")
      (node (ref "CN2") (pin "5") (pinfunction "C14_5") (pintype "bidirectional"))
      (node (ref "RN1") (pin "8") (pinfunction "P$8_8") (pintype "bidirectional"))
      (node (ref "U1") (pin "2") (pinfunction "IN8P_2") (pintype "bidirectional"))
    )
    (net (code "47") (name "Net-(C22-+)") (class "Default")
      (node (ref "C22") (pin "1") (pinfunction "+_1") (pintype "bidirectional"))
      (node (ref "U1") (pin "28") (pinfunction "VCAP1_28") (pintype "bidirectional"))
    )
    (net (code "48") (name "Net-(C30-Pad1)") (class "Default")
      (node (ref "C30") (pin "1") (pinfunction "1_1") (pintype "passive"))
      (node (ref "R10") (pin "2") (pinfunction "2_2") (pintype "passive"))
      (node (ref "R11") (pin "1") (pinfunction "1_1") (pintype "passive"))
    )
    (net (code "49") (name "Net-(RAW_EDA_SIG-P$1)") (class "Default")
      (node (ref "C31") (pin "1") (pinfunction "1_1") (pintype "passive"))
      (node (ref "R14") (pin "2") (pinfunction "2_2") (pintype "passive"))
      (node (ref "R15") (pin "1") (pinfunction "1_1") (pintype "passive"))
      (node (ref "RAW_EDA_SIG") (pin "X") (pinfunction "P$1_X") (pintype "passive"))
    )
    (net (code "50") (name "Net-(U1-BIASIN)") (class "Default")
      (node (ref "C9") (pin "1") (pinfunction "1_1") (pintype "passive"))
      (node (ref "R2") (pin "1") (pinfunction "1_1") (pintype "passive"))
      (node (ref "U1") (pin "62") (pinfunction "BIASIN_62") (pintype "bidirectional"))
      (node (ref "U1") (pin "63") (pinfunction "BIASOUT_63") (pintype "bidirectional"))
    )
    (net (code "51") (name "Net-(U1-GPIO1)") (class "Default")
      (node (ref "R6") (pin "2") (pinfunction "2_2") (pintype "passive"))
      (node (ref "U1") (pin "42") (pinfunction "GPIO1_42") (pintype "bidirectional"))
    )
    (net (code "52") (name "Net-(U1-GPIO2)") (class "Default")
      (node (ref "R5") (pin "2") (pinfunction "2_2") (pintype "passive"))
      (node (ref "U1") (pin "44") (pinfunction "GPIO2_44") (pintype "bidirectional"))
    )
    (net (code "53") (name "Net-(U1-GPIO3)") (class "Default")
      (node (ref "R4") (pin "2") (pinfunction "2_2") (pintype "passive"))
      (node (ref "U1") (pin "45") (pinfunction "GPIO3_45") (pintype "bidirectional"))
    )
    (net (code "54") (name "Net-(U1-GPIO4)") (class "Default")
      (node (ref "R3") (pin "2") (pinfunction "2_2") (pintype "passive"))
      (node (ref "U1") (pin "46") (pinfunction "GPIO4_46") (pintype "bidirectional"))
    )
    (net (code "55") (name "Net-(U1-START)") (class "Default")
      (node (ref "R1") (pin "2") (pinfunction "2_2") (pintype "passive"))
      (node (ref "U1") (pin "38") (pinfunction "START_38") (pintype "bidirectional"))
    )
    (net (code "56") (name "Net-(U1-VCAP2)") (class "Default")
      (node (ref "C20") (pin "1") (pinfunction "1_1") (pintype "passive"))
      (node (ref "U1") (pin "30") (pinfunction "VCAP2_30") (pintype "bidirectional"))
    )
    (net (code "57") (name "Net-(U1-VCAP3)") (class "Default")
      (node (ref "C11") (pin "2") (pinfunction "2_2") (pintype "passive"))
      (node (ref "C12") (pin "2") (pinfunction "2_2") (pintype "passive"))
      (node (ref "U1") (pin "55") (pinfunction "VCAP3_55") (pintype "bidirectional"))
    )
    (net (code "58") (name "Net-(U1-VCAP4)") (class "Default")
      (node (ref "C21") (pin "1") (pinfunction "1_1") (pintype "passive"))
      (node (ref "U1") (pin "26") (pinfunction "VCAP4_26") (pintype "bidirectional"))
    )
    (net (code "59") (name "Net-(U1-VREFP)") (class "Default")
      (node (ref "C15") (pin "2") (pinfunction "2_2") (pintype "passive"))
      (node (ref "C23") (pin "1") (pinfunction "1_1") (pintype "passive"))
      (node (ref "U1") (pin "24") (pinfunction "VREFP_24") (pintype "bidirectional"))
    )
    (net (code "60") (name "Net-(U2-+INA)") (class "Default")
      (node (ref "C26") (pin "1") (pinfunction "1_1") (pintype "passive"))
      (node (ref "R7") (pin "1") (pinfunction "1_1") (pintype "passive"))
      (node (ref "R8") (pin "2") (pinfunction "2_2") (pintype "passive"))
      (node (ref "U2") (pin "3") (pinfunction "+INA_3") (pintype "input"))
    )
    (net (code "61") (name "Net-(U2-+INB)") (class "Default")
      (node (ref "C24") (pin "2") (pinfunction "2_2") (pintype "passive"))
      (node (ref "C25") (pin "1") (pinfunction "1_1") (pintype "passive"))
      (node (ref "C27") (pin "1") (pinfunction "1_1") (pintype "passive"))
      (node (ref "U2") (pin "2") (pinfunction "-INA_2") (pintype "input"))
      (node (ref "U2") (pin "5") (pinfunction "+INB_5") (pintype "input"))
    )
    (net (code "62") (name "Net-(U3-+INA)") (class "Default")
      (node (ref "C28") (pin "1") (pinfunction "1_1") (pintype "passive"))
      (node (ref "R11") (pin "2") (pinfunction "2_2") (pintype "passive"))
      (node (ref "U3") (pin "3") (pinfunction "+INA_3") (pintype "input"))
    )
    (net (code "63") (name "Net-(U3-+INB)") (class "Default")
      (node (ref "R15") (pin "2") (pinfunction "2_2") (pintype "passive"))
      (node (ref "U3") (pin "5") (pinfunction "+INB_5") (pintype "input"))
    )
    (net (code "64") (name "Net-(U3--INA)") (class "Default")
      (node (ref "C29") (pin "1") (pinfunction "1_1") (pintype "passive"))
      (node (ref "R12") (pin "1") (pinfunction "1_1") (pintype "passive"))
      (node (ref "R13") (pin "1") (pinfunction "1_1") (pintype "passive"))
      (node (ref "U3") (pin "2") (pinfunction "-INA_2") (pintype "input"))
    )
    (net (code "65") (name "Net-(U3-OUTA)") (class "Default")
      (node (ref "C29") (pin "2") (pinfunction "2_2") (pintype "passive"))
      (node (ref "C30") (pin "2") (pinfunction "2_2") (pintype "passive"))
      (node (ref "R12") (pin "2") (pinfunction "2_2") (pintype "passive"))
      (node (ref "R14") (pin "1") (pinfunction "1_1") (pintype "passive"))
      (node (ref "U3") (pin "1") (pinfunction "OUTA_1") (pintype "output"))
    )
    (net (code "66") (name "Net-(U4-LED_CATHODE)") (class "Default")
      (node (ref "R16") (pin "2") (pinfunction "2_2") (pintype "passive"))
      (node (ref "U4") (pin "1") (pinfunction "LED_CATHODE_1") (pintype "bidirectional"))
    )
    (net (code "67") (name "Net-(U4-PD2_CATHODE)") (class "Default")
      (node (ref "C16") (pin "1") (pinfunction "1_1") (pintype "passive"))
      (node (ref "R17") (pin "1") (pinfunction "1_1") (pintype "passive"))
      (node (ref "U4") (pin "6") (pinfunction "PD2_CATHODE_6") (pintype "bidirectional"))
      (node (ref "U5") (pin "4") (pinfunction "IN-_4") (pintype "input"))
    )
    (net (code "68") (name "Net-(U12-IN-)") (class "Default")
      (node (ref "C10") (pin "1") (pinfunction "1_1") (pintype "passive"))
      (node (ref "U12") (pin "4") (pinfunction "IN-_4") (pintype "input"))
      (node (ref "U3") (pin "6") (pinfunction "-INB_6") (pintype "input"))
      (node (ref "U3") (pin "7") (pinfunction "OUTB_7") (pintype "output"))
      (node (ref "U4") (pin "3") (pinfunction "PD1_CATHODE_3") (pintype "bidirectional"))
    )
    (net (code "69") (name "Net-(U12-OUT)") (class "Default")
      (node (ref "C10") (pin "2") (pinfunction "2_2") (pintype "passive"))
      (node (ref "R16") (pin "1") (pinfunction "1_1") (pintype "passive"))
      (node (ref "U12") (pin "1") (pinfunction "OUT_1") (pintype "output"))
    )
    (net (code "70") (name "Net-(U13-VISO)") (class "Default")
      (node (ref "C51") (pin "2") (pinfunction "2_2") (pintype "passive"))
      (node (ref "L1") (pin "1") (pinfunction "1_1") (pintype "bidirectional"))
      (node (ref "U13") (pin "6") (pinfunction "VISO_6") (pintype "bidirectional"))
    )
    (net (code "71") (name "PA02_EDA_SIG") (class "Default")
      (node (ref "C16") (pin "2") (pinfunction "2_2") (pintype "passive"))
      (node (ref "J2") (pin "23") (pinfunction "23_23") (pintype "passive"))
      (node (ref "PA02_EDA_SIG") (pin "X") (pinfunction "P$1_X") (pintype "passive"))
      (node (ref "R17") (pin "2") (pinfunction "2_2") (pintype "passive"))
      (node (ref "U5") (pin "1") (pinfunction "OUT_1") (pintype "output"))
    )
    (net (code "72") (name "PA07_DRDY") (class "Default")
      (node (ref "J2") (pin "7") (pinfunction "7_7") (pintype "passive"))
      (node (ref "U1") (pin "47") (pinfunction "~{DRDY}_47") (pintype "bidirectional"))
    )
    (net (code "73") (name "PA16_S1_MOSI") (class "Default")
      (node (ref "J2") (pin "1") (pinfunction "1_1") (pintype "passive"))
      (node (ref "U1") (pin "34") (pinfunction "DIN_34") (pintype "bidirectional"))
    )
    (net (code "74") (name "PA17_S1_SCK") (class "Default")
      (node (ref "J2") (pin "5") (pinfunction "5_5") (pintype "passive"))
      (node (ref "U1") (pin "40") (pinfunction "SCLK_40") (pintype "bidirectional"))
    )
    (net (code "75") (name "PA19_S1_MISO") (class "Default")
      (node (ref "J2") (pin "6") (pinfunction "6_6") (pintype "passive"))
      (node (ref "U1") (pin "43") (pinfunction "DOUT_43") (pintype "bidirectional"))
    )
    (net (code "76") (name "PA20_CS") (class "Default")
      (node (ref "J2") (pin "4") (pinfunction "4_4") (pintype "passive"))
      (node (ref "U1") (pin "39") (pinfunction "~{CS}_39") (pintype "bidirectional"))
    )
    (net (code "77") (name "S0_I2C_SCL") (class "Default")
      (node (ref "J1") (pin "23") (pinfunction "23_23") (pintype "passive"))
      (node (ref "J2") (pin "9") (pinfunction "9_9") (pintype "passive"))
    )
    (net (code "78") (name "S0_I2C_SDA") (class "Default")
      (node (ref "J1") (pin "24") (pinfunction "24_24") (pintype "passive"))
      (node (ref "J2") (pin "8") (pinfunction "8_8") (pintype "passive"))
    )
    (net (code "79") (name "SRB1") (class "Default")
      (node (ref "RN5") (pin "3") (pinfunction "P$3_3") (pintype "bidirectional"))
      (node (ref "U10") (pin "2") (pinfunction "IO2_2") (pintype "bidirectional"))
    )
    (net (code "80") (name "SRB2") (class "Default")
      (node (ref "RN5") (pin "4") (pinfunction "P$4_4") (pintype "bidirectional"))
      (node (ref "U10") (pin "5") (pinfunction "IO4_5") (pintype "bidirectional"))
    )
    (net (code "81") (name "VCC") (class "Default")
      (node (ref "J1") (pin "21") (pinfunction "21_21") (pintype "passive"))
      (node (ref "J1") (pin "22") (pinfunction "22_22") (pintype "passive"))
      (node (ref "J2") (pin "13") (pinfunction "13_13") (pintype "passive"))
      (node (ref "J2") (pin "14") (pinfunction "14_14") (pintype "passive"))
    )
    (net (code "82") (name "_SRB1") (class "Default")
      (node (ref "CN6") (pin "6") (pinfunction "C15_6") (pintype "bidirectional"))
      (node (ref "RN5") (pin "7") (pinfunction "P$7_7") (pintype "bidirectional"))
      (node (ref "U1") (pin "17") (pinfunction "SRB1_17") (pintype "bidirectional"))
    )
    (net (code "83") (name "_SRB2") (class "Default")
      (node (ref "CN6") (pin "5") (pinfunction "C14_5") (pintype "bidirectional"))
      (node (ref "RN5") (pin "8") (pinfunction "P$8_8") (pintype "bidirectional"))
      (node (ref "U1") (pin "18") (pinfunction "SRB2_18") (pintype "bidirectional"))
    )
    (net (code "84") (name "unconnected-(J1-PadMP1)") (class "Default")
      (node (ref "J1") (pin "MP1") (pinfunction "MP1_MP1") (pintype "passive"))
    )
    (net (code "85") (name "unconnected-(J1-PadMP2)") (class "Default")
      (node (ref "J1") (pin "MP2") (pinfunction "MP2_MP2") (pintype "passive"))
    )
    (net (code "86") (name "unconnected-(J2-Pad24)") (class "Default")
      (node (ref "J2") (pin "24") (pinfunction "24_24") (pintype "passive"))
    )
    (net (code "87") (name "unconnected-(J2-PadMP1)") (class "Default")
      (node (ref "J2") (pin "MP1") (pinfunction "MP1_MP1") (pintype "passive"))
    )
    (net (code "88") (name "unconnected-(J2-PadMP2)") (class "Default")
      (node (ref "J2") (pin "MP2") (pinfunction "MP2_MP2") (pintype "passive"))
    )
    (net (code "89") (name "unconnected-(J3-PadMP1)") (class "Default")
      (node (ref "J3") (pin "MP1") (pinfunction "MP1_MP1") (pintype "passive"))
    )
    (net (code "90") (name "unconnected-(J3-PadMP2)") (class "Default")
      (node (ref "J3") (pin "MP2") (pinfunction "MP2_MP2") (pintype "passive"))
    )
    (net (code "91") (name "unconnected-(U1-DAISY_IN-Pad41)") (class "Default")
      (node (ref "U1") (pin "41") (pinfunction "DAISY_IN_41") (pintype "bidirectional"))
    )
    (net (code "92") (name "unconnected-(U1-NC_1-Pad27)") (class "Default")
      (node (ref "U1") (pin "27") (pinfunction "NC_1_27") (pintype "bidirectional"))
    )
    (net (code "93") (name "unconnected-(U1-NC_2-Pad29)") (class "Default")
      (node (ref "U1") (pin "29") (pinfunction "NC_2_29") (pintype "bidirectional"))
    )
    (net (code "94") (name "unconnected-(U1-RESERVED-Pad64)") (class "Default")
      (node (ref "U1") (pin "64") (pinfunction "RESERVED_64") (pintype "bidirectional"))
    )
    (net (code "95") (name "unconnected-(U2-OUTA-Pad1)") (class "Default")
      (node (ref "U2") (pin "1") (pinfunction "OUTA_1") (pintype "output"))
    )
    (net (code "96") (name "unconnected-(U4-NC_1-Pad7)") (class "Default")
      (node (ref "U4") (pin "7") (pinfunction "NC_1_7") (pintype "bidirectional"))
    )
    (net (code "97") (name "unconnected-(U4-NC_2-Pad8)") (class "Default")
      (node (ref "U4") (pin "8") (pinfunction "NC_2_8") (pintype "bidirectional"))
    )
    (net (code "98") (name "unconnected-(U6-IO1-Pad1)") (class "Default")
      (node (ref "U6") (pin "1") (pinfunction "IO1_1") (pintype "bidirectional"))
    )
    (net (code "99") (name "unconnected-(U6-NC-Pad6)") (class "Default")
      (node (ref "U6") (pin "6") (pinfunction "NC_6") (pintype "no_connect"))
    )
    (net (code "100") (name "unconnected-(U7-NC-Pad6)") (class "Default")
      (node (ref "U7") (pin "6") (pinfunction "NC_6") (pintype "no_connect"))
    )
    (net (code "101") (name "unconnected-(U8-NC-Pad6)") (class "Default")
      (node (ref "U8") (pin "6") (pinfunction "NC_6") (pintype "no_connect"))
    )
    (net (code "102") (name "unconnected-(U9-NC-Pad6)") (class "Default")
      (node (ref "U9") (pin "6") (pinfunction "NC_6") (pintype "no_connect"))
    )
    (net (code "103") (name "unconnected-(U10-NC-Pad6)") (class "Default")
      (node (ref "U10") (pin "6") (pinfunction "NC_6") (pintype "no_connect"))
    )
    (net (code "104") (name "unconnected-(U11-IO4-Pad5)") (class "Default")
      (node (ref "U11") (pin "5") (pinfunction "IO4_5") (pintype "bidirectional"))
    )
    (net (code "105") (name "unconnected-(U11-NC-Pad6)") (class "Default")
      (node (ref "U11") (pin "6") (pinfunction "NC_6") (pintype "no_connect"))
    )
  )
)
